# Fonte_de_Tens_o.net
KiCad netlist of a schematic drawn in EAGLE
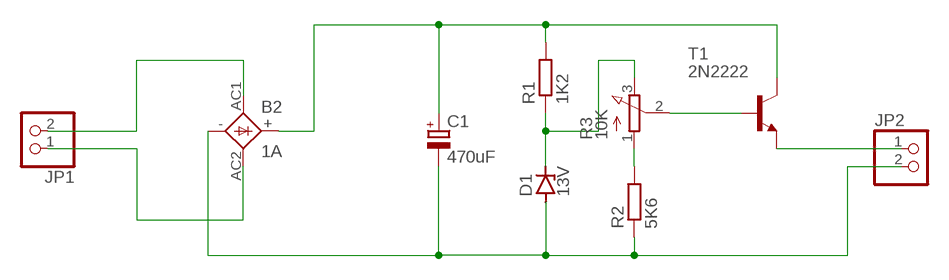
[diagram p0: schematic, sheet 1]

(export (version "E")
  (design (tool "Eeschema 10.0.6"))
  (components
    (comp (ref "B2")
      (value "1A")
      (footprint "eagle-import:GBPC1")
      (libsource (lib "eagle-import") (part "GBPC1"))
    )
    (comp (ref "C1")
      (value "470uF")
      (footprint "eagle-import:E3,5-10")
      (libsource (lib "eagle-import") (part "CPOL-EUE3.5-10"))
    )
    (comp (ref "D1")
      (value "13V")
      (footprint "eagle-import:DO35Z10")
      (libsource (lib "eagle-import") (part "ZENER-DIODEDO35Z10"))
    )
    (comp (ref "JP1")
      (value "PINHD-1X2")
      (footprint "eagle-import:1X02")
      (libsource (lib "eagle-import") (part "PINHD-1X2"))
    )
    (comp (ref "JP2")
      (value "PINHD-1X2")
      (footprint "eagle-import:1X02")
      (libsource (lib "eagle-import") (part "PINHD-1X2"))
    )
    (comp (ref "R1")
      (value "1K2")
      (footprint "eagle-import:0309_12")
      (libsource (lib "eagle-import") (part "R-EU_0309/12"))
    )
    (comp (ref "R2")
      (value "5K6")
      (footprint "eagle-import:0309_12")
      (libsource (lib "eagle-import") (part "R-EU_0309/12"))
    )
    (comp (ref "R3")
      (value "10K")
      (footprint "eagle-import:3RP_1610N")
      (libsource (lib "eagle-import") (part "3RP/1610N"))
    )
    (comp (ref "T1")
      (value "2N2222")
      (footprint "eagle-import:TO18")
      (libsource (lib "eagle-import") (part "2N2222"))
    )
  )
  (nets
    (net (code "1") (name "Net-(B2-Pad-)") (class "Default")
      (node (ref "B2") (pin "-") (pinfunction "-_-") (pintype "passive"))
      (node (ref "C1") (pin "-") (pinfunction "-_-") (pintype "passive"))
      (node (ref "D1") (pin "A") (pinfunction "A_A") (pintype "passive"))
      (node (ref "JP2") (pin "2") (pinfunction "2_2") (pintype "passive"))
      (node (ref "R2") (pin "1") (pinfunction "1_1") (pintype "passive"))
    )
    (net (code "2") (name "Net-(B2-PadAC1)") (class "Default")
      (node (ref "B2") (pin "AC1") (pinfunction "AC1_AC1") (pintype "passive"))
      (node (ref "JP1") (pin "2") (pinfunction "2_2") (pintype "passive"))
    )
    (net (code "3") (name "Net-(B2-PadAC2)") (class "Default")
      (node (ref "B2") (pin "AC2") (pinfunction "AC2_AC2") (pintype "passive"))
      (node (ref "JP1") (pin "1") (pinfunction "1_1") (pintype "passive"))
    )
    (net (code "4") (name "Net-(R3-A)") (class "Default")
      (node (ref "R2") (pin "2") (pinfunction "2_2") (pintype "passive"))
      (node (ref "R3") (pin "1") (pinfunction "A_1") (pintype "passive"))
    )
    (net (code "5") (name "Net-(R3-E)") (class "Default")
      (node (ref "D1") (pin "C") (pinfunction "C_C") (pintype "passive"))
      (node (ref "R1") (pin "1") (pinfunction "1_1") (pintype "passive"))
      (node (ref "R3") (pin "3") (pinfunction "E_3") (pintype "passive"))
    )
    (net (code "6") (name "Net-(R3-S)") (class "Default")
      (node (ref "R3") (pin "2") (pinfunction "S_2") (pintype "passive"))
      (node (ref "T1") (pin "2") (pinfunction "B_2") (pintype "passive"))
    )
    (net (code "7") (name "Net-(T1-C)") (class "Default")
      (node (ref "B2") (pin "+") (pinfunction "+_+") (pintype "passive"))
      (node (ref "C1") (pin "+") (pinfunction "+_+") (pintype "passive"))
      (node (ref "R1") (pin "2") (pinfunction "2_2") (pintype "passive"))
      (node (ref "T1") (pin "3") (pinfunction "C_3") (pintype "passive"))
    )
    (net (code "8") (name "Net-(T1-E)") (class "Default")
      (node (ref "JP2") (pin "1") (pinfunction "1_1") (pintype "passive"))
      (node (ref "T1") (pin "1") (pinfunction "E_1") (pintype "passive"))
    )
  )
)
